# Shield_H-Bridge_v1_716.net
KiCad netlist of a schematic drawn in EAGLE
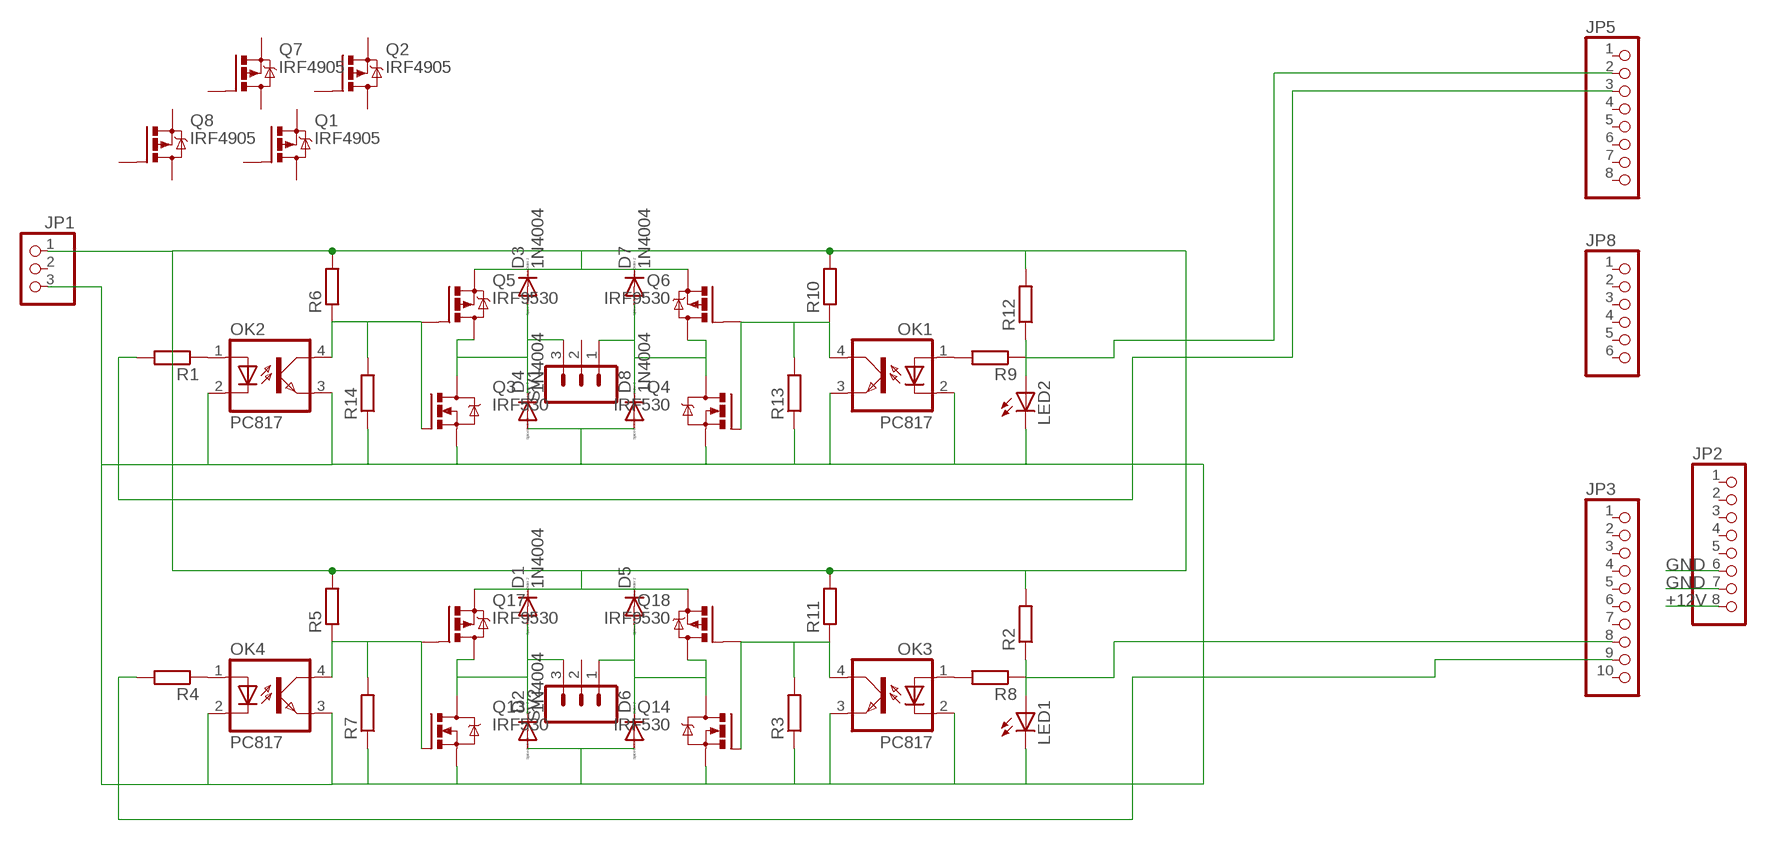
[diagram p0: schematic, sheet 1]

(export (version "E")
  (design (tool "Eeschema 10.0.6"))
  (components
    (comp (ref "D1")
      (value "1N4004")
      (footprint "eagle-import:DO41-10")
      (libsource (lib "eagle-import") (part "1N4004"))
    )
    (comp (ref "D2")
      (value "1N4004")
      (footprint "eagle-import:DO41-10")
      (libsource (lib "eagle-import") (part "1N4004"))
    )
    (comp (ref "D3")
      (value "1N4004")
      (footprint "eagle-import:DO41-10")
      (libsource (lib "eagle-import") (part "1N4004"))
    )
    (comp (ref "D4")
      (value "1N4004")
      (footprint "eagle-import:DO41-10")
      (libsource (lib "eagle-import") (part "1N4004"))
    )
    (comp (ref "D5")
      (value "1N4004")
      (footprint "eagle-import:DO41-10")
      (libsource (lib "eagle-import") (part "1N4004"))
    )
    (comp (ref "D6")
      (value "1N4004")
      (footprint "eagle-import:DO41-10")
      (libsource (lib "eagle-import") (part "1N4004"))
    )
    (comp (ref "D7")
      (value "1N4004")
      (footprint "eagle-import:DO41-10")
      (libsource (lib "eagle-import") (part "1N4004"))
    )
    (comp (ref "D8")
      (value "1N4004")
      (footprint "eagle-import:DO41-10")
      (libsource (lib "eagle-import") (part "1N4004"))
    )
    (comp (ref "JP1")
      (value "PINHD-1X3")
      (footprint "eagle-import:1X03")
      (libsource (lib "eagle-import") (part "PINHD-1X3"))
    )
    (comp (ref "JP2")
      (value "PINHD-1X8")
      (footprint "eagle-import:1X08")
      (libsource (lib "eagle-import") (part "PINHD-1X8"))
    )
    (comp (ref "JP3")
      (value "PINHD-1X10")
      (footprint "eagle-import:1X10")
      (libsource (lib "eagle-import") (part "PINHD-1X10"))
    )
    (comp (ref "JP5")
      (value "PINHD-1X8")
      (footprint "eagle-import:1X08")
      (libsource (lib "eagle-import") (part "PINHD-1X8"))
    )
    (comp (ref "JP8")
      (value "PINHD-1X6")
      (footprint "eagle-import:1X06")
      (libsource (lib "eagle-import") (part "PINHD-1X6"))
    )
    (comp (ref "LED1")
      (value "LED3MM")
      (footprint "eagle-import:LED3MM")
      (libsource (lib "eagle-import") (part "LED3MM"))
    )
    (comp (ref "LED2")
      (value "LED3MM")
      (footprint "eagle-import:LED3MM")
      (libsource (lib "eagle-import") (part "LED3MM"))
    )
    (comp (ref "OK1")
      (value "PC817")
      (footprint "eagle-import:DIL04")
      (fields (field (name "MPN") "PC817X4J000F"))
      (libsource (lib "eagle-import") (part "PC817"))
    )
    (comp (ref "OK2")
      (value "PC817")
      (footprint "eagle-import:DIL04")
      (fields (field (name "MPN") "PC817X4J000F"))
      (libsource (lib "eagle-import") (part "PC817"))
    )
    (comp (ref "OK3")
      (value "PC817")
      (footprint "eagle-import:DIL04")
      (fields (field (name "MPN") "PC817X4J000F"))
      (libsource (lib "eagle-import") (part "PC817"))
    )
    (comp (ref "OK4")
      (value "PC817")
      (footprint "eagle-import:DIL04")
      (fields (field (name "MPN") "PC817X4J000F"))
      (libsource (lib "eagle-import") (part "PC817"))
    )
    (comp (ref "Q1")
      (value "IRF4905")
      (footprint "eagle-import:TO220BH")
      (libsource (lib "eagle-import") (part "IRF4905"))
    )
    (comp (ref "Q2")
      (value "IRF4905")
      (footprint "eagle-import:TO220BH")
      (libsource (lib "eagle-import") (part "IRF4905"))
    )
    (comp (ref "Q3")
      (value "IRF530")
      (footprint "eagle-import:TO220BV")
      (libsource (lib "eagle-import") (part "IRF530"))
    )
    (comp (ref "Q4")
      (value "IRF530")
      (footprint "eagle-import:TO220BV")
      (libsource (lib "eagle-import") (part "IRF530"))
    )
    (comp (ref "Q5")
      (value "IRF9530")
      (footprint "eagle-import:TO220BV")
      (libsource (lib "eagle-import") (part "IRF9530"))
    )
    (comp (ref "Q6")
      (value "IRF9530")
      (footprint "eagle-import:TO220BV")
      (libsource (lib "eagle-import") (part "IRF9530"))
    )
    (comp (ref "Q7")
      (value "IRF4905")
      (footprint "eagle-import:TO220BH")
      (libsource (lib "eagle-import") (part "IRF4905"))
    )
    (comp (ref "Q8")
      (value "IRF4905")
      (footprint "eagle-import:TO220BH")
      (libsource (lib "eagle-import") (part "IRF4905"))
    )
    (comp (ref "Q13")
      (value "IRF530")
      (footprint "eagle-import:TO220BV")
      (libsource (lib "eagle-import") (part "IRF530"))
    )
    (comp (ref "Q14")
      (value "IRF530")
      (footprint "eagle-import:TO220BV")
      (libsource (lib "eagle-import") (part "IRF530"))
    )
    (comp (ref "Q17")
      (value "IRF9530")
      (footprint "eagle-import:TO220BV")
      (libsource (lib "eagle-import") (part "IRF9530"))
    )
    (comp (ref "Q18")
      (value "IRF9530")
      (footprint "eagle-import:TO220BV")
      (libsource (lib "eagle-import") (part "IRF9530"))
    )
    (comp (ref "R1")
      (value "R-EU_0204/7")
      (footprint "eagle-import:0204_7")
      (libsource (lib "eagle-import") (part "R-EU_0204/7"))
    )
    (comp (ref "R2")
      (value "R-EU_0204/5")
      (footprint "eagle-import:0204_5")
      (libsource (lib "eagle-import") (part "R-EU_0204/5"))
    )
    (comp (ref "R3")
      (value "R-EU_0204/7")
      (footprint "eagle-import:0204_7")
      (libsource (lib "eagle-import") (part "R-EU_0204/7"))
    )
    (comp (ref "R4")
      (value "R-EU_0204/7")
      (footprint "eagle-import:0204_7")
      (libsource (lib "eagle-import") (part "R-EU_0204/7"))
    )
    (comp (ref "R5")
      (value "R-EU_0204/7")
      (footprint "eagle-import:0204_7")
      (libsource (lib "eagle-import") (part "R-EU_0204/7"))
    )
    (comp (ref "R6")
      (value "R-EU_0204/7")
      (footprint "eagle-import:0204_7")
      (libsource (lib "eagle-import") (part "R-EU_0204/7"))
    )
    (comp (ref "R7")
      (value "R-EU_0204/7")
      (footprint "eagle-import:0204_7")
      (libsource (lib "eagle-import") (part "R-EU_0204/7"))
    )
    (comp (ref "R8")
      (value "R-EU_0204/7")
      (footprint "eagle-import:0204_7")
      (libsource (lib "eagle-import") (part "R-EU_0204/7"))
    )
    (comp (ref "R9")
      (value "R-EU_0204/7")
      (footprint "eagle-import:0204_7")
      (libsource (lib "eagle-import") (part "R-EU_0204/7"))
    )
    (comp (ref "R10")
      (value "R-EU_0204/7")
      (footprint "eagle-import:0204_7")
      (libsource (lib "eagle-import") (part "R-EU_0204/7"))
    )
    (comp (ref "R11")
      (value "R-EU_0204/7")
      (footprint "eagle-import:0204_7")
      (libsource (lib "eagle-import") (part "R-EU_0204/7"))
    )
    (comp (ref "R12")
      (value "R-EU_0204/5")
      (footprint "eagle-import:0204_5")
      (libsource (lib "eagle-import") (part "R-EU_0204/5"))
    )
    (comp (ref "R13")
      (value "R-EU_0204/7")
      (footprint "eagle-import:0204_7")
      (libsource (lib "eagle-import") (part "R-EU_0204/7"))
    )
    (comp (ref "R14")
      (value "R-EU_0204/7")
      (footprint "eagle-import:0204_7")
      (libsource (lib "eagle-import") (part "R-EU_0204/7"))
    )
    (comp (ref "SV1")
      (value "MA03-1")
      (footprint "eagle-import:MA03-1")
      (libsource (lib "eagle-import") (part "MA03-1"))
    )
    (comp (ref "SV2")
      (value "MA03-1")
      (footprint "eagle-import:MA03-1")
      (libsource (lib "eagle-import") (part "MA03-1"))
    )
  )
  (nets
    (net (code "1") (name "/+12V") (class "Default")
      (node (ref "D1") (pin "C") (pinfunction "C_C") (pintype "passive"))
      (node (ref "D3") (pin "C") (pinfunction "C_C") (pintype "passive"))
      (node (ref "D5") (pin "C") (pinfunction "C_C") (pintype "passive"))
      (node (ref "D7") (pin "C") (pinfunction "C_C") (pintype "passive"))
      (node (ref "JP1") (pin "1") (pinfunction "1_1") (pintype "passive"))
      (node (ref "JP2") (pin "8") (pinfunction "8_8") (pintype "passive"))
      (node (ref "Q17") (pin "S") (pinfunction "S_S") (pintype "passive"))
      (node (ref "Q18") (pin "S") (pinfunction "S_S") (pintype "passive"))
      (node (ref "Q5") (pin "S") (pinfunction "S_S") (pintype "passive"))
      (node (ref "Q6") (pin "S") (pinfunction "S_S") (pintype "passive"))
      (node (ref "R10") (pin "2") (pinfunction "2_2") (pintype "passive"))
      (node (ref "R11") (pin "2") (pinfunction "2_2") (pintype "passive"))
      (node (ref "R12") (pin "2") (pinfunction "2_2") (pintype "passive"))
      (node (ref "R2") (pin "2") (pinfunction "2_2") (pintype "passive"))
      (node (ref "R5") (pin "2") (pinfunction "2_2") (pintype "passive"))
      (node (ref "R6") (pin "2") (pinfunction "2_2") (pintype "passive"))
    )
    (net (code "2") (name "/GND") (class "Default")
      (node (ref "D2") (pin "A") (pinfunction "A_A") (pintype "passive"))
      (node (ref "D4") (pin "A") (pinfunction "A_A") (pintype "passive"))
      (node (ref "D6") (pin "A") (pinfunction "A_A") (pintype "passive"))
      (node (ref "D8") (pin "A") (pinfunction "A_A") (pintype "passive"))
      (node (ref "JP1") (pin "3") (pinfunction "3_3") (pintype "passive"))
      (node (ref "JP2") (pin "6") (pinfunction "6_6") (pintype "passive"))
      (node (ref "JP2") (pin "7") (pinfunction "7_7") (pintype "passive"))
      (node (ref "LED1") (pin "K") (pinfunction "C_K") (pintype "passive"))
      (node (ref "LED2") (pin "K") (pinfunction "C_K") (pintype "passive"))
      (node (ref "OK1") (pin "2") (pinfunction "C_2") (pintype "passive"))
      (node (ref "OK1") (pin "3") (pinfunction "EMIT_3") (pintype "passive"))
      (node (ref "OK2") (pin "2") (pinfunction "C_2") (pintype "passive"))
      (node (ref "OK2") (pin "3") (pinfunction "EMIT_3") (pintype "passive"))
      (node (ref "OK3") (pin "2") (pinfunction "C_2") (pintype "passive"))
      (node (ref "OK3") (pin "3") (pinfunction "EMIT_3") (pintype "passive"))
      (node (ref "OK4") (pin "2") (pinfunction "C_2") (pintype "passive"))
      (node (ref "OK4") (pin "3") (pinfunction "EMIT_3") (pintype "passive"))
      (node (ref "Q13") (pin "S") (pinfunction "S_S") (pintype "passive"))
      (node (ref "Q14") (pin "S") (pinfunction "S_S") (pintype "passive"))
      (node (ref "Q3") (pin "S") (pinfunction "S_S") (pintype "passive"))
      (node (ref "Q4") (pin "S") (pinfunction "S_S") (pintype "passive"))
      (node (ref "R13") (pin "1") (pinfunction "1_1") (pintype "passive"))
      (node (ref "R14") (pin "1") (pinfunction "1_1") (pintype "passive"))
      (node (ref "R3") (pin "1") (pinfunction "1_1") (pintype "passive"))
      (node (ref "R7") (pin "1") (pinfunction "1_1") (pintype "passive"))
    )
    (net (code "3") (name "Net-(D1-PadA)") (class "Default")
      (node (ref "D1") (pin "A") (pinfunction "A_A") (pintype "passive"))
      (node (ref "D2") (pin "C") (pinfunction "C_C") (pintype "passive"))
      (node (ref "Q13") (pin "D") (pinfunction "D_D") (pintype "passive"))
      (node (ref "Q17") (pin "D") (pinfunction "D_D") (pintype "passive"))
      (node (ref "SV2") (pin "3") (pinfunction "3_3") (pintype "passive"))
    )
    (net (code "4") (name "Net-(D3-PadA)") (class "Default")
      (node (ref "D3") (pin "A") (pinfunction "A_A") (pintype "passive"))
      (node (ref "D4") (pin "C") (pinfunction "C_C") (pintype "passive"))
      (node (ref "Q3") (pin "D") (pinfunction "D_D") (pintype "passive"))
      (node (ref "Q5") (pin "D") (pinfunction "D_D") (pintype "passive"))
      (node (ref "SV1") (pin "3") (pinfunction "3_3") (pintype "passive"))
    )
    (net (code "5") (name "Net-(D5-PadA)") (class "Default")
      (node (ref "D5") (pin "A") (pinfunction "A_A") (pintype "passive"))
      (node (ref "D6") (pin "C") (pinfunction "C_C") (pintype "passive"))
      (node (ref "Q14") (pin "D") (pinfunction "D_D") (pintype "passive"))
      (node (ref "Q18") (pin "D") (pinfunction "D_D") (pintype "passive"))
      (node (ref "SV2") (pin "1") (pinfunction "1_1") (pintype "passive"))
    )
    (net (code "6") (name "Net-(D7-PadA)") (class "Default")
      (node (ref "D7") (pin "A") (pinfunction "A_A") (pintype "passive"))
      (node (ref "D8") (pin "C") (pinfunction "C_C") (pintype "passive"))
      (node (ref "Q4") (pin "D") (pinfunction "D_D") (pintype "passive"))
      (node (ref "Q6") (pin "D") (pinfunction "D_D") (pintype "passive"))
      (node (ref "SV1") (pin "1") (pinfunction "1_1") (pintype "passive"))
    )
    (net (code "7") (name "Net-(JP3-Pad8)") (class "Default")
      (node (ref "JP3") (pin "8") (pinfunction "8_8") (pintype "passive"))
      (node (ref "R8") (pin "1") (pinfunction "1_1") (pintype "passive"))
    )
    (net (code "8") (name "Net-(JP3-Pad9)") (class "Default")
      (node (ref "JP3") (pin "9") (pinfunction "9_9") (pintype "passive"))
      (node (ref "R4") (pin "2") (pinfunction "2_2") (pintype "passive"))
    )
    (net (code "9") (name "Net-(JP5-Pad2)") (class "Default")
      (node (ref "JP5") (pin "2") (pinfunction "2_2") (pintype "passive"))
      (node (ref "R9") (pin "1") (pinfunction "1_1") (pintype "passive"))
    )
    (net (code "10") (name "Net-(JP5-Pad3)") (class "Default")
      (node (ref "JP5") (pin "3") (pinfunction "3_3") (pintype "passive"))
      (node (ref "R1") (pin "2") (pinfunction "2_2") (pintype "passive"))
    )
    (net (code "11") (name "Net-(LED1-PadA)") (class "Default")
      (node (ref "LED1") (pin "A") (pinfunction "A_A") (pintype "passive"))
      (node (ref "R2") (pin "1") (pinfunction "1_1") (pintype "passive"))
    )
    (net (code "12") (name "Net-(LED2-PadA)") (class "Default")
      (node (ref "LED2") (pin "A") (pinfunction "A_A") (pintype "passive"))
      (node (ref "R12") (pin "1") (pinfunction "1_1") (pintype "passive"))
    )
    (net (code "13") (name "Net-(OK1-A)") (class "Default")
      (node (ref "OK1") (pin "1") (pinfunction "A_1") (pintype "passive"))
      (node (ref "R9") (pin "2") (pinfunction "2_2") (pintype "passive"))
    )
    (net (code "14") (name "Net-(OK1-COL)") (class "Default")
      (node (ref "OK1") (pin "4") (pinfunction "COL_4") (pintype "passive"))
      (node (ref "Q4") (pin "G") (pinfunction "G_G") (pintype "passive"))
      (node (ref "Q6") (pin "G") (pinfunction "G_G") (pintype "passive"))
      (node (ref "R10") (pin "1") (pinfunction "1_1") (pintype "passive"))
      (node (ref "R13") (pin "2") (pinfunction "2_2") (pintype "passive"))
    )
    (net (code "15") (name "Net-(OK2-A)") (class "Default")
      (node (ref "OK2") (pin "1") (pinfunction "A_1") (pintype "passive"))
      (node (ref "R1") (pin "1") (pinfunction "1_1") (pintype "passive"))
    )
    (net (code "16") (name "Net-(OK2-COL)") (class "Default")
      (node (ref "OK2") (pin "4") (pinfunction "COL_4") (pintype "passive"))
      (node (ref "Q3") (pin "G") (pinfunction "G_G") (pintype "passive"))
      (node (ref "Q5") (pin "G") (pinfunction "G_G") (pintype "passive"))
      (node (ref "R14") (pin "2") (pinfunction "2_2") (pintype "passive"))
      (node (ref "R6") (pin "1") (pinfunction "1_1") (pintype "passive"))
    )
    (net (code "17") (name "Net-(OK3-A)") (class "Default")
      (node (ref "OK3") (pin "1") (pinfunction "A_1") (pintype "passive"))
      (node (ref "R8") (pin "2") (pinfunction "2_2") (pintype "passive"))
    )
    (net (code "18") (name "Net-(OK3-COL)") (class "Default")
      (node (ref "OK3") (pin "4") (pinfunction "COL_4") (pintype "passive"))
      (node (ref "Q14") (pin "G") (pinfunction "G_G") (pintype "passive"))
      (node (ref "Q18") (pin "G") (pinfunction "G_G") (pintype "passive"))
      (node (ref "R11") (pin "1") (pinfunction "1_1") (pintype "passive"))
      (node (ref "R3") (pin "2") (pinfunction "2_2") (pintype "passive"))
    )
    (net (code "19") (name "Net-(OK4-A)") (class "Default")
      (node (ref "OK4") (pin "1") (pinfunction "A_1") (pintype "passive"))
      (node (ref "R4") (pin "1") (pinfunction "1_1") (pintype "passive"))
    )
    (net (code "20") (name "Net-(OK4-COL)") (class "Default")
      (node (ref "OK4") (pin "4") (pinfunction "COL_4") (pintype "passive"))
      (node (ref "Q13") (pin "G") (pinfunction "G_G") (pintype "passive"))
      (node (ref "Q17") (pin "G") (pinfunction "G_G") (pintype "passive"))
      (node (ref "R5") (pin "1") (pinfunction "1_1") (pintype "passive"))
      (node (ref "R7") (pin "2") (pinfunction "2_2") (pintype "passive"))
    )
    (net (code "21") (name "unconnected-(JP1-Pad2)") (class "Default")
      (node (ref "JP1") (pin "2") (pinfunction "2_2") (pintype "passive"))
    )
    (net (code "22") (name "unconnected-(JP2-Pad1)") (class "Default")
      (node (ref "JP2") (pin "1") (pinfunction "1_1") (pintype "passive"))
    )
    (net (code "23") (name "unconnected-(JP2-Pad2)") (class "Default")
      (node (ref "JP2") (pin "2") (pinfunction "2_2") (pintype "passive"))
    )
    (net (code "24") (name "unconnected-(JP2-Pad3)") (class "Default")
      (node (ref "JP2") (pin "3") (pinfunction "3_3") (pintype "passive"))
    )
    (net (code "25") (name "unconnected-(JP2-Pad4)") (class "Default")
      (node (ref "JP2") (pin "4") (pinfunction "4_4") (pintype "passive"))
    )
    (net (code "26") (name "unconnected-(JP2-Pad5)") (class "Default")
      (node (ref "JP2") (pin "5") (pinfunction "5_5") (pintype "passive"))
    )
    (net (code "27") (name "unconnected-(JP3-Pad1)") (class "Default")
      (node (ref "JP3") (pin "1") (pinfunction "1_1") (pintype "passive"))
    )
    (net (code "28") (name "unconnected-(JP3-Pad2)") (class "Default")
      (node (ref "JP3") (pin "2") (pinfunction "2_2") (pintype "passive"))
    )
    (net (code "29") (name "unconnected-(JP3-Pad3)") (class "Default")
      (node (ref "JP3") (pin "3") (pinfunction "3_3") (pintype "passive"))
    )
    (net (code "30") (name "unconnected-(JP3-Pad4)") (class "Default")
      (node (ref "JP3") (pin "4") (pinfunction "4_4") (pintype "passive"))
    )
    (net (code "31") (name "unconnected-(JP3-Pad5)") (class "Default")
      (node (ref "JP3") (pin "5") (pinfunction "5_5") (pintype "passive"))
    )
    (net (code "32") (name "unconnected-(JP3-Pad6)") (class "Default")
      (node (ref "JP3") (pin "6") (pinfunction "6_6") (pintype "passive"))
    )
    (net (code "33") (name "unconnected-(JP3-Pad7)") (class "Default")
      (node (ref "JP3") (pin "7") (pinfunction "7_7") (pintype "passive"))
    )
    (net (code "34") (name "unconnected-(JP3-Pad10)") (class "Default")
      (node (ref "JP3") (pin "10") (pinfunction "10_10") (pintype "passive"))
    )
    (net (code "35") (name "unconnected-(JP5-Pad1)") (class "Default")
      (node (ref "JP5") (pin "1") (pinfunction "1_1") (pintype "passive"))
    )
    (net (code "36") (name "unconnected-(JP5-Pad4)") (class "Default")
      (node (ref "JP5") (pin "4") (pinfunction "4_4") (pintype "passive"))
    )
    (net (code "37") (name "unconnected-(JP5-Pad5)") (class "Default")
      (node (ref "JP5") (pin "5") (pinfunction "5_5") (pintype "passive"))
    )
    (net (code "38") (name "unconnected-(JP5-Pad6)") (class "Default")
      (node (ref "JP5") (pin "6") (pinfunction "6_6") (pintype "passive"))
    )
    (net (code "39") (name "unconnected-(JP5-Pad7)") (class "Default")
      (node (ref "JP5") (pin "7") (pinfunction "7_7") (pintype "passive"))
    )
    (net (code "40") (name "unconnected-(JP5-Pad8)") (class "Default")
      (node (ref "JP5") (pin "8") (pinfunction "8_8") (pintype "passive"))
    )
    (net (code "41") (name "unconnected-(JP8-Pad1)") (class "Default")
      (node (ref "JP8") (pin "1") (pinfunction "1_1") (pintype "passive"))
    )
    (net (code "42") (name "unconnected-(JP8-Pad2)") (class "Default")
      (node (ref "JP8") (pin "2") (pinfunction "2_2") (pintype "passive"))
    )
    (net (code "43") (name "unconnected-(JP8-Pad3)") (class "Default")
      (node (ref "JP8") (pin "3") (pinfunction "3_3") (pintype "passive"))
    )
    (net (code "44") (name "unconnected-(JP8-Pad4)") (class "Default")
      (node (ref "JP8") (pin "4") (pinfunction "4_4") (pintype "passive"))
    )
    (net (code "45") (name "unconnected-(JP8-Pad5)") (class "Default")
      (node (ref "JP8") (pin "5") (pinfunction "5_5") (pintype "passive"))
    )
    (net (code "46") (name "unconnected-(JP8-Pad6)") (class "Default")
      (node (ref "JP8") (pin "6") (pinfunction "6_6") (pintype "passive"))
    )
    (net (code "47") (name "unconnected-(Q1-PadD)") (class "Default")
      (node (ref "Q1") (pin "D") (pinfunction "D_D") (pintype "passive"))
    )
    (net (code "48") (name "unconnected-(Q1-PadG)") (class "Default")
      (node (ref "Q1") (pin "G") (pinfunction "G_G") (pintype "passive"))
    )
    (net (code "49") (name "unconnected-(Q1-PadS)") (class "Default")
      (node (ref "Q1") (pin "S") (pinfunction "S_S") (pintype "passive"))
    )
    (net (code "50") (name "unconnected-(Q2-PadD)") (class "Default")
      (node (ref "Q2") (pin "D") (pinfunction "D_D") (pintype "passive"))
    )
    (net (code "51") (name "unconnected-(Q2-PadG)") (class "Default")
      (node (ref "Q2") (pin "G") (pinfunction "G_G") (pintype "passive"))
    )
    (net (code "52") (name "unconnected-(Q2-PadS)") (class "Default")
      (node (ref "Q2") (pin "S") (pinfunction "S_S") (pintype "passive"))
    )
    (net (code "53") (name "unconnected-(Q7-PadD)") (class "Default")
      (node (ref "Q7") (pin "D") (pinfunction "D_D") (pintype "passive"))
    )
    (net (code "54") (name "unconnected-(Q7-PadG)") (class "Default")
      (node (ref "Q7") (pin "G") (pinfunction "G_G") (pintype "passive"))
    )
    (net (code "55") (name "unconnected-(Q7-PadS)") (class "Default")
      (node (ref "Q7") (pin "S") (pinfunction "S_S") (pintype "passive"))
    )
    (net (code "56") (name "unconnected-(Q8-PadD)") (class "Default")
      (node (ref "Q8") (pin "D") (pinfunction "D_D") (pintype "passive"))
    )
    (net (code "57") (name "unconnected-(Q8-PadG)") (class "Default")
      (node (ref "Q8") (pin "G") (pinfunction "G_G") (pintype "passive"))
    )
    (net (code "58") (name "unconnected-(Q8-PadS)") (class "Default")
      (node (ref "Q8") (pin "S") (pinfunction "S_S") (pintype "passive"))
    )
    (net (code "59") (name "unconnected-(SV1-Pad2)") (class "Default")
      (node (ref "SV1") (pin "2") (pinfunction "2_2") (pintype "passive"))
    )
    (net (code "60") (name "unconnected-(SV2-Pad2)") (class "Default")
      (node (ref "SV2") (pin "2") (pinfunction "2_2") (pintype "passive"))
    )
  )
)
